# MI_06_07_08_MCU.net
KiCad netlist of a schematic drawn in Altium Designer
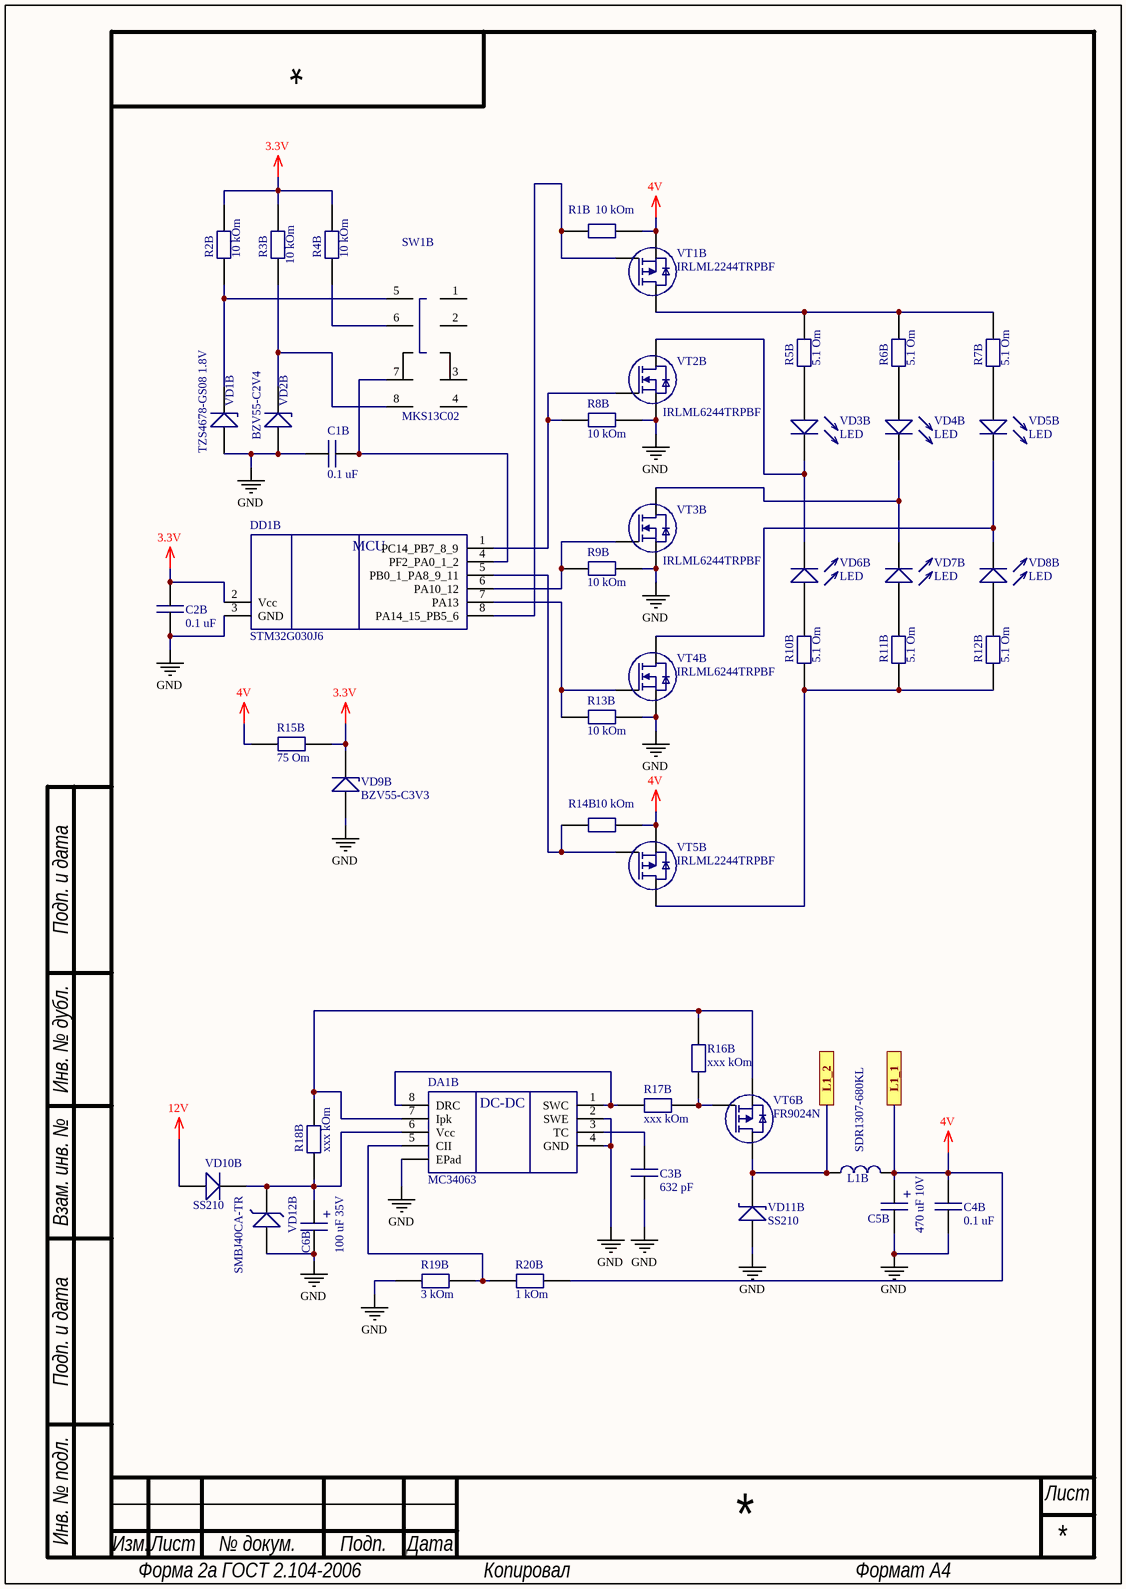
[diagram p0: MI_06_07_08_MCU.SchDoc]

(export (version "E")
  (design (tool "Eeschema 10.0.6"))
  (components
    (comp (ref "C1B")
      (value "0.1 uF")
      (footprint "CAP1206")
      (fields (field (name "Comment") "Capacitor"))
      (libsource (lib "my_library") (part "Capacitor"))
    )
    (comp (ref "C2B")
      (value "0.1 uF")
      (footprint "CAP1206")
      (fields (field (name "Comment") "Capacitor"))
      (libsource (lib "my_library") (part "Capacitor"))
    )
    (comp (ref "C3B")
      (value "632 pF")
      (footprint "CAP1206")
      (fields (field (name "Comment") "Capacitor"))
      (libsource (lib "my_library") (part "Capacitor"))
    )
    (comp (ref "C4B")
      (value "0.1 uF")
      (footprint "CAP1206")
      (fields (field (name "Comment") "Capacitor"))
      (libsource (lib "my_library") (part "Capacitor"))
    )
    (comp (ref "C5B")
      (value "470 uF 10V")
      (footprint "CAP6.3x7.7")
      (fields (field (name "Comment") "Capacitor_Polar"))
      (libsource (lib "my_library") (part "Capacitor_Polar"))
    )
    (comp (ref "C6B")
      (value "100 uF 35V")
      (footprint "CAP6.3x7.7")
      (fields (field (name "Comment") "Capacitor_Polar"))
      (libsource (lib "my_library") (part "Capacitor_Polar"))
    )
    (comp (ref "DA1B")
      (value "MC34063")
      (footprint "SOIC-8-EPad")
      (libsource (lib "my_library") (part "MC34063"))
    )
    (comp (ref "DD1B")
      (value "STM32G030J6")
      (footprint "SOIC-8")
      (libsource (lib "my_library") (part "STM32G030J6"))
    )
    (comp (ref "L1B")
      (value "SDR1307-680KL")
      (footprint "SDR1307")
      (fields (field (name "Comment") "coil"))
      (libsource (lib "my_library") (part "coil"))
    )
    (comp (ref "R1B")
      (value "10 kOm")
      (footprint "RES1206")
      (fields (field (name "Comment") "Resistor"))
      (libsource (lib "my_library") (part "Resistor"))
    )
    (comp (ref "R2B")
      (value "10 kOm")
      (footprint "RES1206")
      (fields (field (name "Comment") "Resistor"))
      (libsource (lib "my_library") (part "Resistor"))
    )
    (comp (ref "R3B")
      (value "10 kOm")
      (footprint "RES1206")
      (fields (field (name "Comment") "Resistor"))
      (libsource (lib "my_library") (part "Resistor"))
    )
    (comp (ref "R4B")
      (value "10 kOm")
      (footprint "RES1206")
      (fields (field (name "Comment") "Resistor"))
      (libsource (lib "my_library") (part "Resistor"))
    )
    (comp (ref "R5B")
      (value "5.1 Om")
      (footprint "RES1206")
      (fields (field (name "Comment") "Resistor"))
      (libsource (lib "my_library") (part "Resistor"))
    )
    (comp (ref "R6B")
      (value "5.1 Om")
      (footprint "RES1206")
      (fields (field (name "Comment") "Resistor"))
      (libsource (lib "my_library") (part "Resistor"))
    )
    (comp (ref "R7B")
      (value "5.1 Om")
      (footprint "RES1206")
      (fields (field (name "Comment") "Resistor"))
      (libsource (lib "my_library") (part "Resistor"))
    )
    (comp (ref "R8B")
      (value "10 kOm")
      (footprint "RES1206")
      (fields (field (name "Comment") "Resistor"))
      (libsource (lib "my_library") (part "Resistor"))
    )
    (comp (ref "R9B")
      (value "10 kOm")
      (footprint "RES1206")
      (fields (field (name "Comment") "Resistor"))
      (libsource (lib "my_library") (part "Resistor"))
    )
    (comp (ref "R10B")
      (value "5.1 Om")
      (footprint "RES1206")
      (fields (field (name "Comment") "Resistor"))
      (libsource (lib "my_library") (part "Resistor"))
    )
    (comp (ref "R11B")
      (value "5.1 Om")
      (footprint "RES1206")
      (fields (field (name "Comment") "Resistor"))
      (libsource (lib "my_library") (part "Resistor"))
    )
    (comp (ref "R12B")
      (value "5.1 Om")
      (footprint "RES1206")
      (fields (field (name "Comment") "Resistor"))
      (libsource (lib "my_library") (part "Resistor"))
    )
    (comp (ref "R13B")
      (value "10 kOm")
      (footprint "RES1206")
      (fields (field (name "Comment") "Resistor"))
      (libsource (lib "my_library") (part "Resistor"))
    )
    (comp (ref "R14B")
      (value "10 kOm")
      (footprint "RES1206")
      (fields (field (name "Comment") "Resistor"))
      (libsource (lib "my_library") (part "Resistor"))
    )
    (comp (ref "R15B")
      (value "75 Om")
      (footprint "RES1206")
      (fields (field (name "Comment") "Resistor"))
      (libsource (lib "my_library") (part "Resistor"))
    )
    (comp (ref "R16B")
      (value "xxx kOm")
      (footprint "RES1206")
      (fields (field (name "Comment") "Resistor"))
      (libsource (lib "my_library") (part "Resistor"))
    )
    (comp (ref "R17B")
      (value "xxx kOm")
      (footprint "RES1206")
      (fields (field (name "Comment") "Resistor"))
      (libsource (lib "my_library") (part "Resistor"))
    )
    (comp (ref "R18B")
      (value "xxx kOm")
      (footprint "RES1206")
      (fields (field (name "Comment") "Resistor"))
      (libsource (lib "my_library") (part "Resistor"))
    )
    (comp (ref "R19B")
      (value "3 kOm")
      (footprint "RES1206")
      (fields (field (name "Comment") "Resistor"))
      (libsource (lib "my_library") (part "Resistor"))
    )
    (comp (ref "R20B")
      (value "1 kOm")
      (footprint "RES1206")
      (fields (field (name "Comment") "Resistor"))
      (libsource (lib "my_library") (part "Resistor"))
    )
    (comp (ref "SW1B")
      (value "MKS13C02")
      (footprint "K3-2346S-K1")
      (fields (field (name "Comment") "K3-2346S-K1"))
      (libsource (lib "my_library") (part "K3-2346S-K1"))
    )
    (comp (ref "VD1B")
      (value "TZS4678-GS08 1.8V")
      (footprint "minimelf")
      (fields (field (name "Comment") "Zenner"))
      (libsource (lib "") (part "Zenner_1"))
    )
    (comp (ref "VD2B")
      (value "BZV55-C2V4")
      (footprint "minimelf")
      (fields (field (name "Comment") "Zenner"))
      (libsource (lib "") (part "Zenner_1"))
    )
    (comp (ref "VD3B") (value "LED") (footprint "LED_MAJAK2") (libsource (lib "my_library") (part "LED")))
    (comp (ref "VD4B") (value "LED") (footprint "LED_MAJAK2") (libsource (lib "my_library") (part "LED")))
    (comp (ref "VD5B") (value "LED") (footprint "LED_MAJAK2") (libsource (lib "my_library") (part "LED")))
    (comp (ref "VD6B") (value "LED") (footprint "LED_MAJAK2") (libsource (lib "my_library") (part "LED")))
    (comp (ref "VD7B") (value "LED") (footprint "LED_MAJAK2") (libsource (lib "my_library") (part "LED")))
    (comp (ref "VD8B") (value "LED") (footprint "LED_MAJAK2") (libsource (lib "my_library") (part "LED")))
    (comp (ref "VD9B")
      (value "BZV55-C3V3")
      (footprint "minimelf")
      (fields (field (name "Comment") "Zenner"))
      (libsource (lib "my_library") (part "Zenner"))
    )
    (comp (ref "VD10B")
      (value "SS210")
      (footprint "SMB1")
      (fields (field (name "Comment") "Diode"))
      (libsource (lib "my_library") (part "Diode"))
    )
    (comp (ref "VD11B")
      (value "SS210")
      (footprint "SMB1")
      (fields (field (name "Comment") "Schottky"))
      (libsource (lib "my_library") (part "Schottky"))
    )
    (comp (ref "VD12B")
      (value "SMBJ40CA-TR")
      (footprint "SMB1")
      (fields (field (name "Comment") "Suppressor"))
      (libsource (lib "my_library") (part "Suppressor"))
    )
    (comp (ref "VT1B")
      (value "IRLML2244TRPBF")
      (footprint "SOT 23")
      (fields (field (name "Comment") "MOSFET-P"))
      (libsource (lib "my_library") (part "MOSFET-P"))
    )
    (comp (ref "VT2B")
      (value "IRLML6244TRPBF")
      (footprint "SOT 23")
      (fields (field (name "Comment") "MOSFET-N"))
      (libsource (lib "my_library") (part "MOSFET-N"))
    )
    (comp (ref "VT3B")
      (value "IRLML6244TRPBF")
      (footprint "SOT 23")
      (fields (field (name "Comment") "MOSFET-N"))
      (libsource (lib "my_library") (part "MOSFET-N"))
    )
    (comp (ref "VT4B")
      (value "IRLML6244TRPBF")
      (footprint "SOT 23")
      (fields (field (name "Comment") "MOSFET-N"))
      (libsource (lib "my_library") (part "MOSFET-N"))
    )
    (comp (ref "VT5B")
      (value "IRLML2244TRPBF")
      (footprint "SOT 23")
      (fields (field (name "Comment") "MOSFET-P"))
      (libsource (lib "my_library") (part "MOSFET-P"))
    )
    (comp (ref "VT6B")
      (value "FR9024N")
      (footprint "D PAK")
      (fields (field (name "Comment") "MOSFET-P"))
      (libsource (lib "my_library") (part "MOSFET-P"))
    )
  )
  (nets
    (net (code "1") (name "/L1_2") (class "Default")
      (node (ref "L1B") (pin "1") (pinfunction "1_1") (pintype "passive"))
      (node (ref "VD11B") (pin "1") (pinfunction "1_1") (pintype "passive"))
      (node (ref "VT6B") (pin "D") (pintype "passive"))
    )
    (net (code "2") (name "3.3V") (class "Default")
      (node (ref "C2B") (pin "2") (pinfunction "2_2") (pintype "passive"))
      (node (ref "DD1B") (pin "2") (pinfunction "Vcc_2") (pintype "passive"))
      (node (ref "R15B") (pin "1") (pinfunction "1_1") (pintype "passive"))
      (node (ref "R2B") (pin "1") (pinfunction "1_1") (pintype "passive"))
      (node (ref "R3B") (pin "1") (pinfunction "1_1") (pintype "passive"))
      (node (ref "R4B") (pin "1") (pinfunction "1_1") (pintype "passive"))
      (node (ref "VD9B") (pin "1") (pinfunction "1_1") (pintype "passive"))
    )
    (net (code "3") (name "4V") (class "Default")
      (node (ref "C4B") (pin "1") (pinfunction "1_1") (pintype "passive"))
      (node (ref "C5B") (pin "1") (pinfunction "1_1") (pintype "passive"))
      (node (ref "L1B") (pin "2") (pinfunction "2_2") (pintype "passive"))
      (node (ref "R14B") (pin "2") (pinfunction "2_2") (pintype "passive"))
      (node (ref "R15B") (pin "2") (pinfunction "2_2") (pintype "passive"))
      (node (ref "R1B") (pin "2") (pinfunction "2_2") (pintype "passive"))
      (node (ref "R20B") (pin "2") (pinfunction "2_2") (pintype "passive"))
      (node (ref "VT1B") (pin "S") (pintype "passive"))
      (node (ref "VT5B") (pin "S") (pintype "passive"))
    )
    (net (code "4") (name "12V") (class "Default")
      (node (ref "VD10B") (pin "1") (pinfunction "1_1") (pintype "passive"))
    )
    (net (code "5") (name "GND") (class "Default")
      (node (ref "C1B") (pin "2") (pinfunction "2_2") (pintype "passive"))
      (node (ref "C2B") (pin "1") (pinfunction "1_1") (pintype "passive"))
      (node (ref "C3B") (pin "2") (pinfunction "2_2") (pintype "passive"))
      (node (ref "C4B") (pin "2") (pinfunction "2_2") (pintype "passive"))
      (node (ref "C5B") (pin "2") (pinfunction "2_2") (pintype "passive"))
      (node (ref "C6B") (pin "2") (pinfunction "2_2") (pintype "passive"))
      (node (ref "DA1B") (pin "0") (pinfunction "EPad_0") (pintype "passive"))
      (node (ref "DA1B") (pin "2") (pinfunction "SWE_2") (pintype "passive"))
      (node (ref "DA1B") (pin "4") (pinfunction "GND_4") (pintype "passive"))
      (node (ref "DD1B") (pin "3") (pinfunction "GND_3") (pintype "passive"))
      (node (ref "R13B") (pin "2") (pinfunction "2_2") (pintype "passive"))
      (node (ref "R19B") (pin "2") (pinfunction "2_2") (pintype "passive"))
      (node (ref "R8B") (pin "2") (pinfunction "2_2") (pintype "passive"))
      (node (ref "R9B") (pin "2") (pinfunction "2_2") (pintype "passive"))
      (node (ref "VD11B") (pin "2") (pinfunction "2_2") (pintype "passive"))
      (node (ref "VD12B") (pin "2") (pinfunction "2_2") (pintype "passive"))
      (node (ref "VD1B") (pin "1") (pinfunction "1_1") (pintype "passive"))
      (node (ref "VD2B") (pin "1") (pinfunction "1_1") (pintype "passive"))
      (node (ref "VD9B") (pin "2") (pinfunction "2_2") (pintype "passive"))
      (node (ref "VT2B") (pin "S") (pintype "passive"))
      (node (ref "VT3B") (pin "S") (pintype "passive"))
      (node (ref "VT4B") (pin "S") (pintype "passive"))
    )
    (net (code "6") (name "Net-(DA1B-CII)") (class "Default")
      (node (ref "DA1B") (pin "5") (pinfunction "CII_5") (pintype "passive"))
      (node (ref "R19B") (pin "1") (pinfunction "1_1") (pintype "passive"))
      (node (ref "R20B") (pin "1") (pinfunction "1_1") (pintype "passive"))
    )
    (net (code "7") (name "Net-(DA1B-DRC)") (class "Default")
      (node (ref "DA1B") (pin "1") (pinfunction "SWC_1") (pintype "passive"))
      (node (ref "DA1B") (pin "8") (pinfunction "DRC_8") (pintype "passive"))
      (node (ref "R17B") (pin "2") (pinfunction "2_2") (pintype "passive"))
    )
    (net (code "8") (name "Net-(DA1B-Ipk)") (class "Default")
      (node (ref "DA1B") (pin "7") (pinfunction "Ipk_7") (pintype "passive"))
      (node (ref "R16B") (pin "1") (pinfunction "1_1") (pintype "passive"))
      (node (ref "R18B") (pin "1") (pinfunction "1_1") (pintype "passive"))
      (node (ref "VT6B") (pin "S") (pintype "passive"))
    )
    (net (code "9") (name "Net-(DA1B-TC)") (class "Default")
      (node (ref "C3B") (pin "1") (pinfunction "1_1") (pintype "passive"))
      (node (ref "DA1B") (pin "3") (pinfunction "TC_3") (pintype "passive"))
    )
    (net (code "10") (name "Net-(DA1B-Vcc)") (class "Default")
      (node (ref "C6B") (pin "1") (pinfunction "1_1") (pintype "passive"))
      (node (ref "DA1B") (pin "6") (pinfunction "Vcc_6") (pintype "passive"))
      (node (ref "R18B") (pin "2") (pinfunction "2_2") (pintype "passive"))
      (node (ref "VD10B") (pin "3") (pinfunction "3_3") (pintype "passive"))
      (node (ref "VD12B") (pin "1") (pinfunction "1_1") (pintype "passive"))
    )
    (net (code "11") (name "Net-(DD1B-PA10_12)") (class "Default")
      (node (ref "DD1B") (pin "6") (pinfunction "PA10_12_6") (pintype "passive"))
      (node (ref "R9B") (pin "1") (pinfunction "1_1") (pintype "passive"))
      (node (ref "VT3B") (pin "G") (pintype "passive"))
    )
    (net (code "12") (name "Net-(DD1B-PA13)") (class "Default")
      (node (ref "DD1B") (pin "7") (pinfunction "PA13_7") (pintype "passive"))
      (node (ref "R13B") (pin "1") (pinfunction "1_1") (pintype "passive"))
      (node (ref "VT4B") (pin "G") (pintype "passive"))
    )
    (net (code "13") (name "Net-(DD1B-PA14_15_PB5_6)") (class "Default")
      (node (ref "DD1B") (pin "8") (pinfunction "PA14_15_PB5_6_8") (pintype "passive"))
      (node (ref "R1B") (pin "1") (pinfunction "1_1") (pintype "passive"))
      (node (ref "VT1B") (pin "G") (pintype "passive"))
    )
    (net (code "14") (name "Net-(DD1B-PB0_1_PA8_9_11)") (class "Default")
      (node (ref "DD1B") (pin "5") (pinfunction "PB0_1_PA8_9_11_5") (pintype "passive"))
      (node (ref "R14B") (pin "1") (pinfunction "1_1") (pintype "passive"))
      (node (ref "VT5B") (pin "G") (pintype "passive"))
    )
    (net (code "15") (name "Net-(DD1B-PC14_PB7_8_9)") (class "Default")
      (node (ref "DD1B") (pin "1") (pinfunction "PC14_PB7_8_9_1") (pintype "passive"))
      (node (ref "R8B") (pin "1") (pinfunction "1_1") (pintype "passive"))
      (node (ref "VT2B") (pin "G") (pintype "passive"))
    )
    (net (code "16") (name "Net-(DD1B-PF2_PA0_1_2)") (class "Default")
      (node (ref "C1B") (pin "1") (pinfunction "1_1") (pintype "passive"))
      (node (ref "DD1B") (pin "4") (pinfunction "PF2_PA0_1_2_4") (pintype "passive"))
      (node (ref "SW1B") (pin "7") (pinfunction "7_7") (pintype "passive"))
    )
    (net (code "17") (name "Net-(R2B-Pad2)") (class "Default")
      (node (ref "R2B") (pin "2") (pinfunction "2_2") (pintype "passive"))
      (node (ref "SW1B") (pin "5") (pinfunction "5_5") (pintype "passive"))
      (node (ref "VD1B") (pin "3") (pinfunction "3_3") (pintype "passive"))
    )
    (net (code "18") (name "Net-(R3B-Pad2)") (class "Default")
      (node (ref "R3B") (pin "2") (pinfunction "2_2") (pintype "passive"))
      (node (ref "SW1B") (pin "8") (pinfunction "8_8") (pintype "passive"))
      (node (ref "VD2B") (pin "3") (pinfunction "3_3") (pintype "passive"))
    )
    (net (code "19") (name "Net-(R4B-Pad2)") (class "Default")
      (node (ref "R4B") (pin "2") (pinfunction "2_2") (pintype "passive"))
      (node (ref "SW1B") (pin "6") (pinfunction "7_6") (pintype "passive"))
    )
    (net (code "20") (name "Net-(R5B-Pad1)") (class "Default")
      (node (ref "R5B") (pin "1") (pinfunction "1_1") (pintype "passive"))
      (node (ref "R6B") (pin "1") (pinfunction "1_1") (pintype "passive"))
      (node (ref "R7B") (pin "1") (pinfunction "1_1") (pintype "passive"))
      (node (ref "VT1B") (pin "D") (pintype "passive"))
    )
    (net (code "21") (name "Net-(R5B-Pad2)") (class "Default")
      (node (ref "R5B") (pin "2") (pinfunction "2_2") (pintype "passive"))
      (node (ref "VD3B") (pin "2") (pinfunction "2_2") (pintype "passive"))
    )
    (net (code "22") (name "Net-(R6B-Pad2)") (class "Default")
      (node (ref "R6B") (pin "2") (pinfunction "2_2") (pintype "passive"))
      (node (ref "VD4B") (pin "2") (pinfunction "2_2") (pintype "passive"))
    )
    (net (code "23") (name "Net-(R7B-Pad2)") (class "Default")
      (node (ref "R7B") (pin "2") (pinfunction "2_2") (pintype "passive"))
      (node (ref "VD5B") (pin "2") (pinfunction "2_2") (pintype "passive"))
    )
    (net (code "24") (name "Net-(R10B-Pad1)") (class "Default")
      (node (ref "R10B") (pin "1") (pinfunction "1_1") (pintype "passive"))
      (node (ref "VD6B") (pin "2") (pinfunction "2_2") (pintype "passive"))
    )
    (net (code "25") (name "Net-(R10B-Pad2)") (class "Default")
      (node (ref "R10B") (pin "2") (pinfunction "2_2") (pintype "passive"))
      (node (ref "R11B") (pin "2") (pinfunction "2_2") (pintype "passive"))
      (node (ref "R12B") (pin "2") (pinfunction "2_2") (pintype "passive"))
      (node (ref "VT5B") (pin "D") (pintype "passive"))
    )
    (net (code "26") (name "Net-(R11B-Pad1)") (class "Default")
      (node (ref "R11B") (pin "1") (pinfunction "1_1") (pintype "passive"))
      (node (ref "VD7B") (pin "2") (pinfunction "2_2") (pintype "passive"))
    )
    (net (code "27") (name "Net-(R12B-Pad1)") (class "Default")
      (node (ref "R12B") (pin "1") (pinfunction "1_1") (pintype "passive"))
      (node (ref "VD8B") (pin "2") (pinfunction "2_2") (pintype "passive"))
    )
    (net (code "28") (name "Net-(R16B-Pad2)") (class "Default")
      (node (ref "R16B") (pin "2") (pinfunction "2_2") (pintype "passive"))
      (node (ref "R17B") (pin "1") (pinfunction "1_1") (pintype "passive"))
      (node (ref "VT6B") (pin "G") (pintype "passive"))
    )
    (net (code "29") (name "Net-(VD3B-Pad1)") (class "Default")
      (node (ref "VD3B") (pin "1") (pinfunction "1_1") (pintype "passive"))
      (node (ref "VD6B") (pin "1") (pinfunction "1_1") (pintype "passive"))
      (node (ref "VT2B") (pin "D") (pintype "passive"))
    )
    (net (code "30") (name "Net-(VD4B-Pad1)") (class "Default")
      (node (ref "VD4B") (pin "1") (pinfunction "1_1") (pintype "passive"))
      (node (ref "VD7B") (pin "1") (pinfunction "1_1") (pintype "passive"))
      (node (ref "VT3B") (pin "D") (pintype "passive"))
    )
    (net (code "31") (name "Net-(VD5B-Pad1)") (class "Default")
      (node (ref "VD5B") (pin "1") (pinfunction "1_1") (pintype "passive"))
      (node (ref "VD8B") (pin "1") (pinfunction "1_1") (pintype "passive"))
      (node (ref "VT4B") (pin "D") (pintype "passive"))
    )
    (net (code "32") (name "unconnected-(SW1B-Pad1)") (class "Default")
      (node (ref "SW1B") (pin "1") (pinfunction "1_1") (pintype "passive"))
    )
    (net (code "33") (name "unconnected-(SW1B-Pad2)") (class "Default")
      (node (ref "SW1B") (pin "2") (pinfunction "2_2") (pintype "passive"))
    )
    (net (code "34") (name "unconnected-(SW1B-Pad3)") (class "Default")
      (node (ref "SW1B") (pin "3") (pinfunction "3_3") (pintype "passive"))
    )
    (net (code "35") (name "unconnected-(SW1B-Pad4)") (class "Default")
      (node (ref "SW1B") (pin "4") (pinfunction "4_4") (pintype "passive"))
    )
  )
)
